# PushButtonYellow.net
KiCad netlist of a schematic drawn in Altium Designer
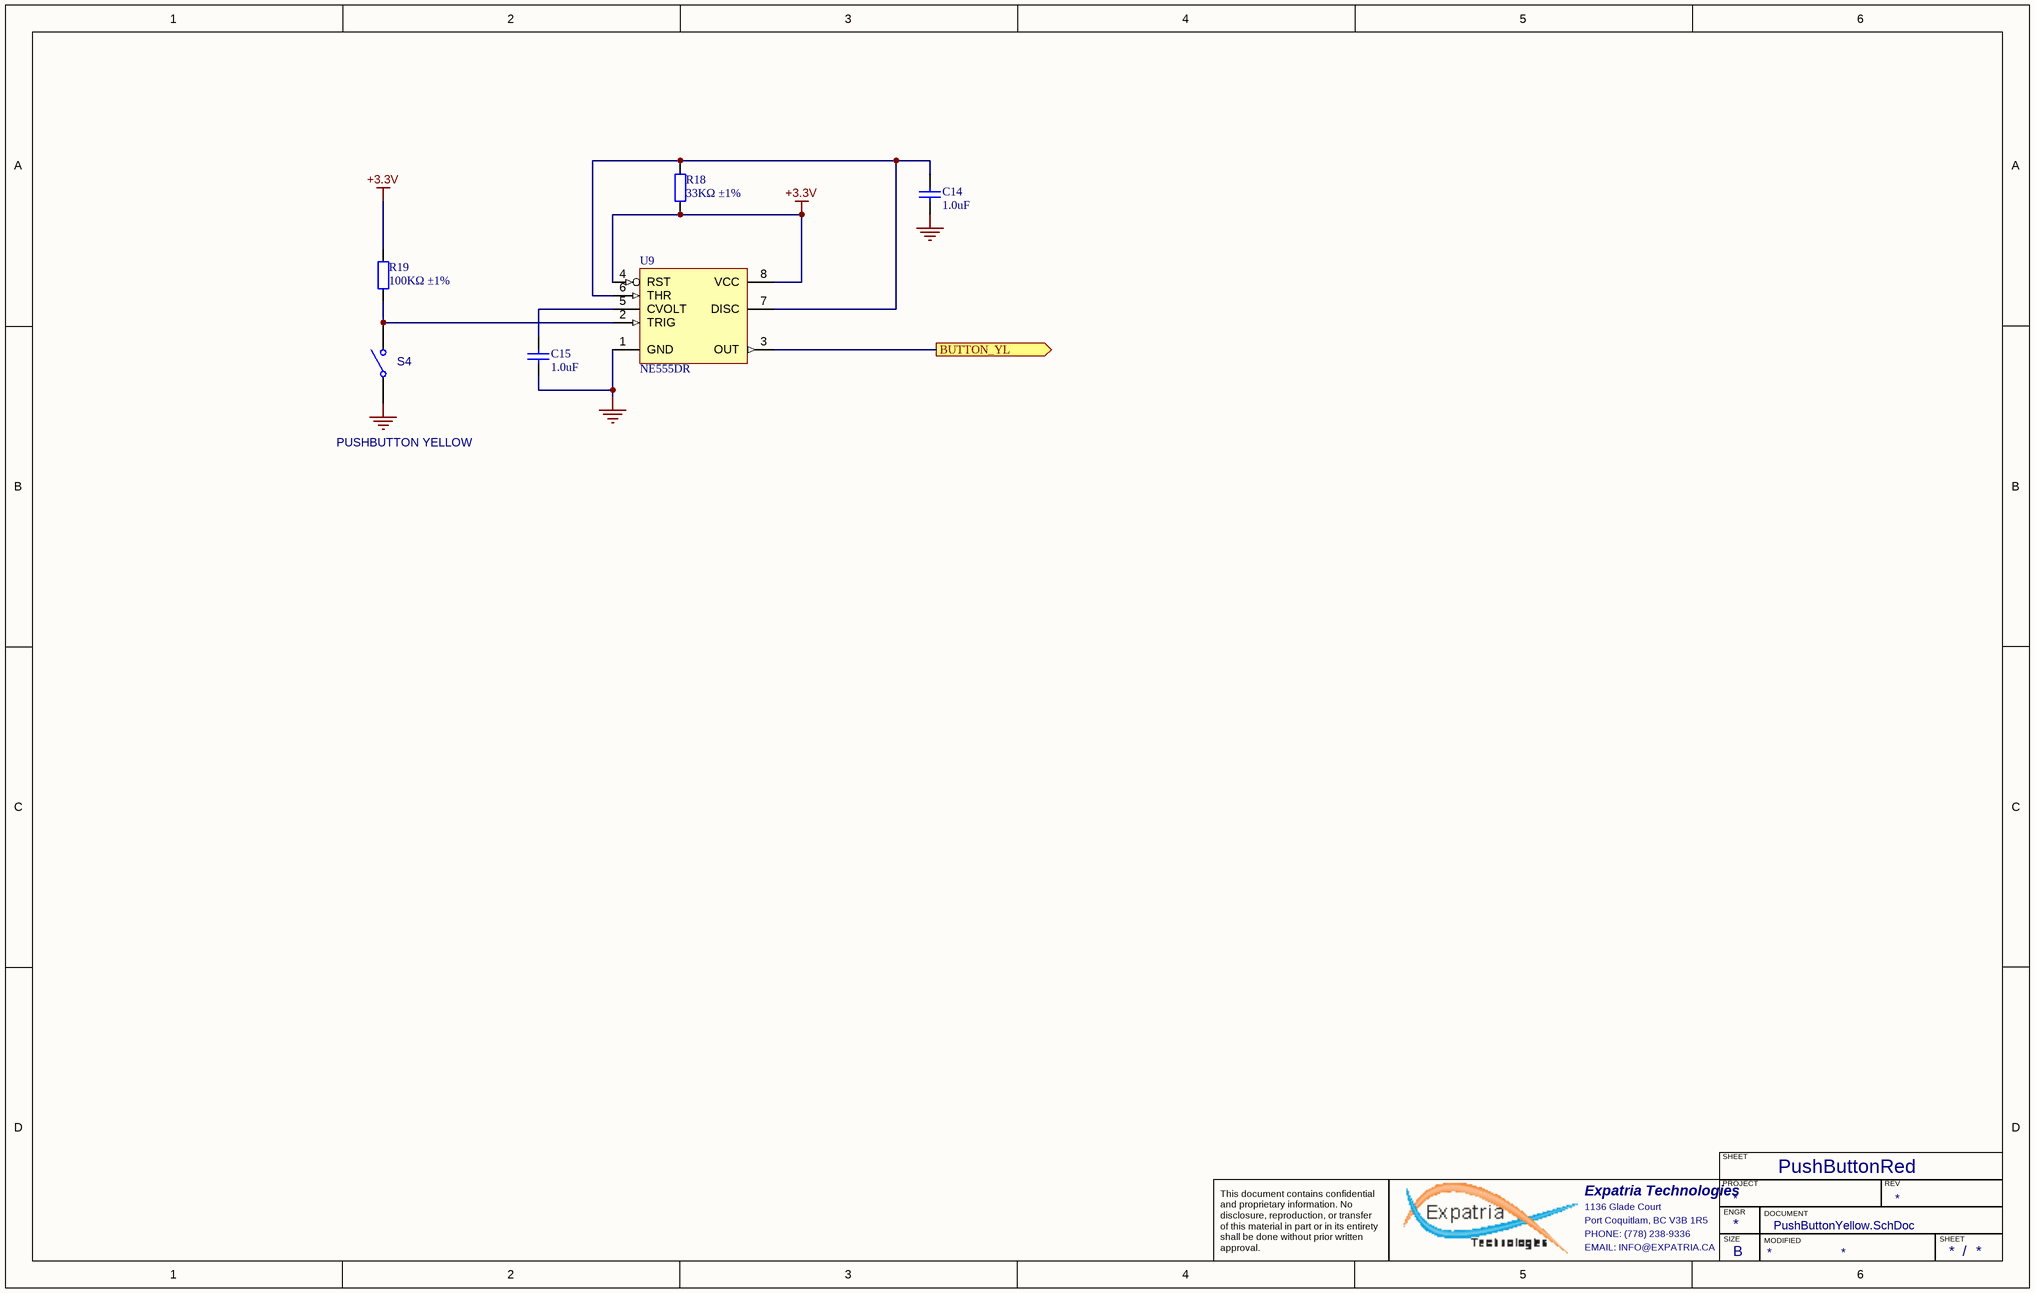
[diagram p0: PushButtonYellow.SchDoc]

(export (version "E")
  (design (tool "Eeschema 10.0.6"))
  (components
    (comp (ref "C14")
      (value "1.0uF")
      (footprint "0402_C")
      (description "Chip capacitor")
      (fields
        (field (name "MANUFACTURER") "Samsung Electro-Mechanics")
        (field (name "PARTNUMBER") "CL05A105KA5NQNC")
      )
      (libsource (lib "Cap") (part "0402 1.0uF (105) 10% 25V"))
    )
    (comp (ref "C15")
      (value "1.0uF")
      (footprint "0402_C")
      (description "Chip capacitor")
      (fields
        (field (name "MANUFACTURER") "Samsung Electro-Mechanics")
        (field (name "PARTNUMBER") "CL05A105KA5NQNC")
      )
      (libsource (lib "Cap") (part "0402 1.0uF (105) 10% 25V"))
    )
    (comp (ref "R18")
      (value "33KΩ ±1%")
      (footprint "0402_R")
      (description "Chip resistor")
      (fields (field (name "MANUFACTURER") "Uniroyal Elec") (field (name "PARTNUMBER") "0402WGF3302TCE"))
      (libsource (lib "RES") (part "0402 33K (3302) 1%"))
    )
    (comp (ref "R19")
      (value "100KΩ ±1%")
      (footprint "0402_R")
      (description "Chip resistor")
      (fields (field (name "MANUFACTURER") "Uniroyal Elec") (field (name "PARTNUMBER") "0402WGF1003TCE"))
      (libsource (lib "RES") (part "0402 100K (1003) 1%"))
    )
    (comp (ref "S4")
      (value "PUSHBUTTON YELLOW")
      (footprint "D6C10F1LFS_YELLOW")
      (description "SWITCH PUSH SPST-NO 0.1A 32V RED")
      (libsource (lib "bluebell") (part "D6R40 F1 LFS"))
    )
    (comp (ref "U9")
      (value "NE555DR")
      (footprint "SOIC-8_150mil")
      (description "时基集成")
      (libsource (lib "IC") (part "NE555DR_[C7593]"))
    )
  )
  (nets
    (net (code "1") (name "+3.3V") (class "Default")
      (node (ref "R18") (pin "1") (pinfunction "1_1") (pintype "passive"))
      (node (ref "R19") (pin "2") (pinfunction "2_2") (pintype "passive"))
      (node (ref "U9") (pin "4") (pinfunction "RST_4") (pintype "input"))
      (node (ref "U9") (pin "8") (pinfunction "VCC_8") (pintype "power_in"))
    )
    (net (code "2") (name "/BUTTON_YL") (class "Default")
      (node (ref "U9") (pin "3") (pinfunction "OUT_3") (pintype "output"))
    )
    (net (code "3") (name "GND") (class "Default")
      (node (ref "C14") (pin "1") (pinfunction "1_1") (pintype "passive"))
      (node (ref "C15") (pin "2") (pinfunction "2_2") (pintype "passive"))
      (node (ref "S4") (pin "1") (pinfunction "COMMON_1") (pintype "passive"))
      (node (ref "U9") (pin "1") (pinfunction "GND_1") (pintype "power_in"))
    )
    (net (code "4") (name "Net-(S4-NO)") (class "Default")
      (node (ref "R19") (pin "1") (pinfunction "1_1") (pintype "passive"))
      (node (ref "S4") (pin "2") (pinfunction "NO_2") (pintype "passive"))
      (node (ref "U9") (pin "2") (pinfunction "TRIG_2") (pintype "input"))
    )
    (net (code "5") (name "Net-(U9-CVOLT)") (class "Default")
      (node (ref "C15") (pin "1") (pinfunction "1_1") (pintype "passive"))
      (node (ref "U9") (pin "5") (pinfunction "CVOLT_5") (pintype "passive"))
    )
    (net (code "6") (name "Net-(U9-DISC)") (class "Default")
      (node (ref "C14") (pin "2") (pinfunction "2_2") (pintype "passive"))
      (node (ref "R18") (pin "2") (pinfunction "2_2") (pintype "passive"))
      (node (ref "U9") (pin "6") (pinfunction "THR_6") (pintype "input"))
      (node (ref "U9") (pin "7") (pinfunction "DISC_7") (pintype "open_collector"))
    )
  )
)
